# Schematic.net
KiCad netlist of a schematic drawn in Altium Designer
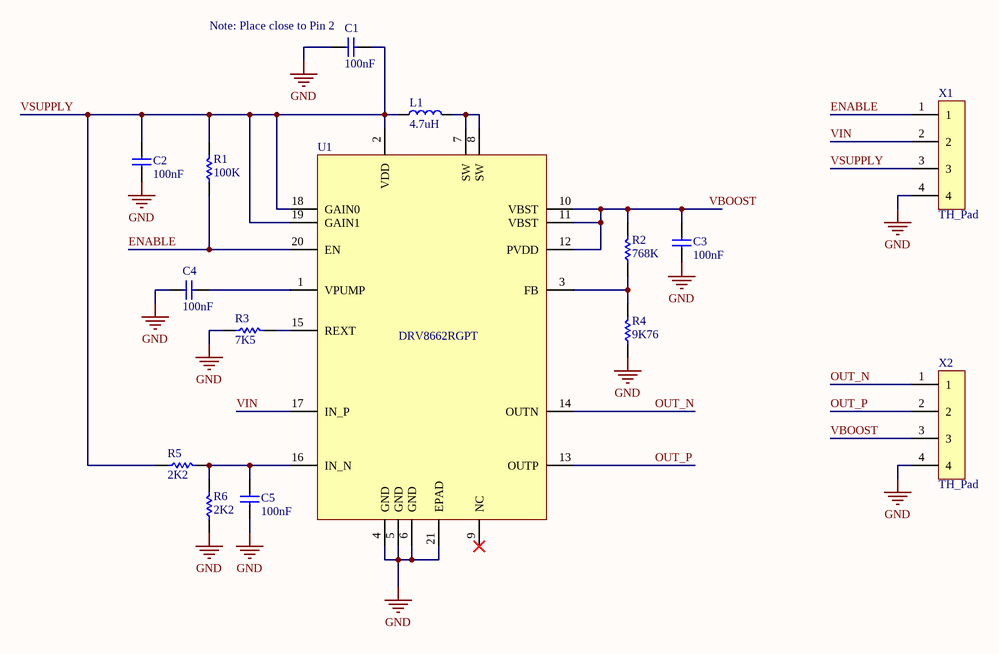
[diagram p0: Schematic.SchDoc]

(export (version "E")
  (design (tool "Eeschema 10.0.6"))
  (components
    (comp (ref "C1")
      (value "100nF")
      (footprint "CAP 0603/1608")
      (description "CAPACITOR 0603 100nF 25V 10%")
      (fields
        (field (name "MANUFACTURER") "TDK")
        (field (name "MANUFACTURER PART NUMBER") "CGA3E2X7R1E104K080AA")
      )
      (libsource (lib "PiezoDrive") (part "CGA3E2X7R1E104K080AA"))
    )
    (comp (ref "C2")
      (value "100nF")
      (footprint "CAP 0603/1608")
      (description "CAPACITOR 0603 100nF 25V 10%")
      (fields
        (field (name "MANUFACTURER") "TDK")
        (field (name "MANUFACTURER PART NUMBER") "CGA3E2X7R1E104K080AA")
      )
      (libsource (lib "PiezoDrive") (part "CGA3E2X7R1E104K080AA"))
    )
    (comp (ref "C3")
      (value "100nF")
      (footprint "CAP 1206/3216")
      (description "CAPACITOR 1206 100nF 250V X7R 10%")
      (fields
        (field (name "MANUFACTURER") "Murata")
        (field (name "MANUFACTURER PART NUMBER") "GRM31CR72E104KW03L")
      )
      (libsource (lib "PiezoDrive") (part "GRM31CR72E104KW03L"))
    )
    (comp (ref "C4")
      (value "100nF")
      (footprint "CAP 0603/1608")
      (description "CAPACITOR 0603 100nF 25V 10%")
      (fields
        (field (name "MANUFACTURER") "TDK")
        (field (name "MANUFACTURER PART NUMBER") "CGA3E2X7R1E104K080AA")
      )
      (libsource (lib "PiezoDrive") (part "CGA3E2X7R1E104K080AA"))
    )
    (comp (ref "C5")
      (value "100nF")
      (footprint "CAP 0603/1608")
      (description "CAPACITOR 0603 100nF 25V 10%")
      (fields
        (field (name "MANUFACTURER") "TDK")
        (field (name "MANUFACTURER PART NUMBER") "CGA3E2X7R1E104K080AA")
      )
      (libsource (lib "PiezoDrive") (part "CGA3E2X7R1E104K080AA"))
    )
    (comp (ref "L1")
      (value "4.7uH")
      (footprint "COILCRAFT_LPS4018")
      (description "INDUCTOR 4.7µH 1.3A")
      (fields
        (field (name "MANUFACTURER") "Coilcraft")
        (field (name "MANUFACTURER PART NUMBER") "LPS4018-472MRB")
      )
      (libsource (lib "PiezoDrive") (part "LPS4018-472MRB"))
    )
    (comp (ref "R1")
      (value "100K")
      (footprint "RES 0603/1608")
      (description "RESISTOR 0603 100K 1%")
      (fields
        (field (name "MANUFACTURER") "Panasonic")
        (field (name "MANUFACTURER PART NUMBER") "ERJ3EKF1003V")
      )
      (libsource (lib "PiezoDrive") (part "ERJ3EKF1003V"))
    )
    (comp (ref "R2")
      (value "768K")
      (footprint "RES 0603/1608")
      (description "RESISTOR 0603 768K 1%")
      (fields
        (field (name "MANUFACTURER") "Panasonic")
        (field (name "MANUFACTURER PART NUMBER") "ERJ-3EKF7683V")
      )
      (libsource (lib "PiezoDrive") (part "ERJ3EKF7683V"))
    )
    (comp (ref "R3")
      (value "7K5")
      (footprint "RES 0603/1608")
      (description "RESISTOR 0603 7.5K 1%")
      (fields
        (field (name "MANUFACTURER") "Panasonic")
        (field (name "MANUFACTURER PART NUMBER") "ERJ-3EKF7501V")
      )
      (libsource (lib "PiezoDrive") (part "ERJ3EKF7501V"))
    )
    (comp (ref "R4")
      (value "9K76")
      (footprint "RES 0603/1608")
      (description "RESISTOR 0603 9.76K 1%")
      (fields
        (field (name "MANUFACTURER") "Panasonic")
        (field (name "MANUFACTURER PART NUMBER") "ERJ-3EKF9761V")
      )
      (libsource (lib "PiezoDrive") (part "ERJ3EKF9761V"))
    )
    (comp (ref "R5")
      (value "2K2")
      (footprint "RES 0603/1608")
      (description "RESISTOR 0603 2.2K 1%")
      (fields
        (field (name "MANUFACTURER") "Panasonic")
        (field (name "MANUFACTURER PART NUMBER") "ERJ-3EKF2201V")
      )
      (libsource (lib "PiezoDrive") (part "ERJ3EKF2201V"))
    )
    (comp (ref "R6")
      (value "2K2")
      (footprint "RES 0603/1608")
      (description "RESISTOR 0603 2.2K 1%")
      (fields
        (field (name "MANUFACTURER") "Panasonic")
        (field (name "MANUFACTURER PART NUMBER") "ERJ-3EKF2201V")
      )
      (libsource (lib "PiezoDrive") (part "ERJ3EKF2201V"))
    )
    (comp (ref "U1")
      (value "DRV8662RGPT")
      (footprint "QFN-20 4x4MM")
      (description "PIEZO HAPTIC DRIVER")
      (fields (field (name "MANUFACTURER") "Texas Instruments"))
      (libsource (lib "PiezoDrive") (part "DRV8662RGPT"))
    )
    (comp (ref "X1")
      (value "TH_Pad")
      (footprint "1X4 TH_PAD")
      (description "1X4 2.54MM TH Pad")
      (libsource (lib "PiezoDrive") (part "TH_Pad"))
    )
    (comp (ref "X2")
      (value "TH_Pad")
      (footprint "1X4 TH_PAD")
      (description "1X4 2.54MM TH Pad")
      (libsource (lib "PiezoDrive") (part "TH_Pad"))
    )
  )
  (nets
    (net (code "1") (name "/ENABLE") (class "Default")
      (node (ref "R1") (pin "1") (pintype "passive"))
      (node (ref "U1") (pin "20") (pinfunction "EN_20") (pintype "passive"))
      (node (ref "X1") (pin "1") (pinfunction "1_1") (pintype "passive"))
    )
    (net (code "2") (name "/OUT_N") (class "Default")
      (node (ref "U1") (pin "14") (pinfunction "OUTN_14") (pintype "passive"))
      (node (ref "X2") (pin "1") (pinfunction "1_1") (pintype "passive"))
    )
    (net (code "3") (name "/OUT_P") (class "Default")
      (node (ref "U1") (pin "13") (pinfunction "OUTP_13") (pintype "passive"))
      (node (ref "X2") (pin "2") (pinfunction "2_2") (pintype "passive"))
    )
    (net (code "4") (name "/VBOOST") (class "Default")
      (node (ref "C3") (pin "2") (pinfunction "2_2") (pintype "passive"))
      (node (ref "R2") (pin "2") (pintype "passive"))
      (node (ref "U1") (pin "10") (pinfunction "VBST_10") (pintype "passive"))
      (node (ref "U1") (pin "11") (pinfunction "VBST_11") (pintype "passive"))
      (node (ref "U1") (pin "12") (pinfunction "PVDD_12") (pintype "passive"))
      (node (ref "X2") (pin "3") (pinfunction "3_3") (pintype "passive"))
    )
    (net (code "5") (name "/VIN") (class "Default")
      (node (ref "U1") (pin "17") (pinfunction "IN_P_17") (pintype "passive"))
      (node (ref "X1") (pin "2") (pinfunction "2_2") (pintype "passive"))
    )
    (net (code "6") (name "/VSUPPLY") (class "Default")
      (node (ref "C1") (pin "2") (pinfunction "2_2") (pintype "passive"))
      (node (ref "C2") (pin "2") (pinfunction "2_2") (pintype "passive"))
      (node (ref "L1") (pin "1") (pinfunction "1_1") (pintype "passive"))
      (node (ref "R1") (pin "2") (pintype "passive"))
      (node (ref "R5") (pin "1") (pintype "passive"))
      (node (ref "U1") (pin "18") (pinfunction "GAIN0_18") (pintype "passive"))
      (node (ref "U1") (pin "19") (pinfunction "GAIN1_19") (pintype "passive"))
      (node (ref "U1") (pin "2") (pinfunction "VDD_2") (pintype "passive"))
      (node (ref "X1") (pin "3") (pinfunction "3_3") (pintype "passive"))
    )
    (net (code "7") (name "GND") (class "Default")
      (node (ref "C1") (pin "1") (pinfunction "1_1") (pintype "passive"))
      (node (ref "C2") (pin "1") (pinfunction "1_1") (pintype "passive"))
      (node (ref "C3") (pin "1") (pinfunction "1_1") (pintype "passive"))
      (node (ref "C4") (pin "2") (pinfunction "2_2") (pintype "passive"))
      (node (ref "C5") (pin "2") (pinfunction "2_2") (pintype "passive"))
      (node (ref "R3") (pin "1") (pintype "passive"))
      (node (ref "R4") (pin "1") (pintype "passive"))
      (node (ref "R6") (pin "1") (pintype "passive"))
      (node (ref "U1") (pin "21") (pinfunction "EPAD_21") (pintype "passive"))
      (node (ref "U1") (pin "4") (pinfunction "GND_4") (pintype "passive"))
      (node (ref "U1") (pin "5") (pinfunction "GND_5") (pintype "passive"))
      (node (ref "U1") (pin "6") (pinfunction "GND_6") (pintype "passive"))
      (node (ref "X1") (pin "4") (pinfunction "4_4") (pintype "passive"))
      (node (ref "X2") (pin "4") (pinfunction "4_4") (pintype "passive"))
    )
    (net (code "8") (name "Net-(L1-Pad2)") (class "Default")
      (node (ref "L1") (pin "2") (pinfunction "2_2") (pintype "passive"))
      (node (ref "U1") (pin "7") (pinfunction "SW_7") (pintype "passive"))
      (node (ref "U1") (pin "8") (pinfunction "SW_8") (pintype "passive"))
    )
    (net (code "9") (name "Net-(U1-FB)") (class "Default")
      (node (ref "R2") (pin "1") (pintype "passive"))
      (node (ref "R4") (pin "2") (pintype "passive"))
      (node (ref "U1") (pin "3") (pinfunction "FB_3") (pintype "passive"))
    )
    (net (code "10") (name "Net-(U1-IN_N)") (class "Default")
      (node (ref "C5") (pin "1") (pinfunction "1_1") (pintype "passive"))
      (node (ref "R5") (pin "2") (pintype "passive"))
      (node (ref "R6") (pin "2") (pintype "passive"))
      (node (ref "U1") (pin "16") (pinfunction "IN_N_16") (pintype "passive"))
    )
    (net (code "11") (name "Net-(U1-REXT)") (class "Default")
      (node (ref "R3") (pin "2") (pintype "passive"))
      (node (ref "U1") (pin "15") (pinfunction "REXT_15") (pintype "passive"))
    )
    (net (code "12") (name "Net-(U1-VPUMP)") (class "Default")
      (node (ref "C4") (pin "1") (pinfunction "1_1") (pintype "passive"))
      (node (ref "U1") (pin "1") (pinfunction "VPUMP_1") (pintype "passive"))
    )
    (net (code "13") (name "unconnected-(U1-NC-Pad9)") (class "Default")
      (node (ref "U1") (pin "9") (pinfunction "NC_9") (pintype "passive+no_connect"))
    )
  )
)
